# V1.net
KiCad netlist of a schematic drawn in EAGLE
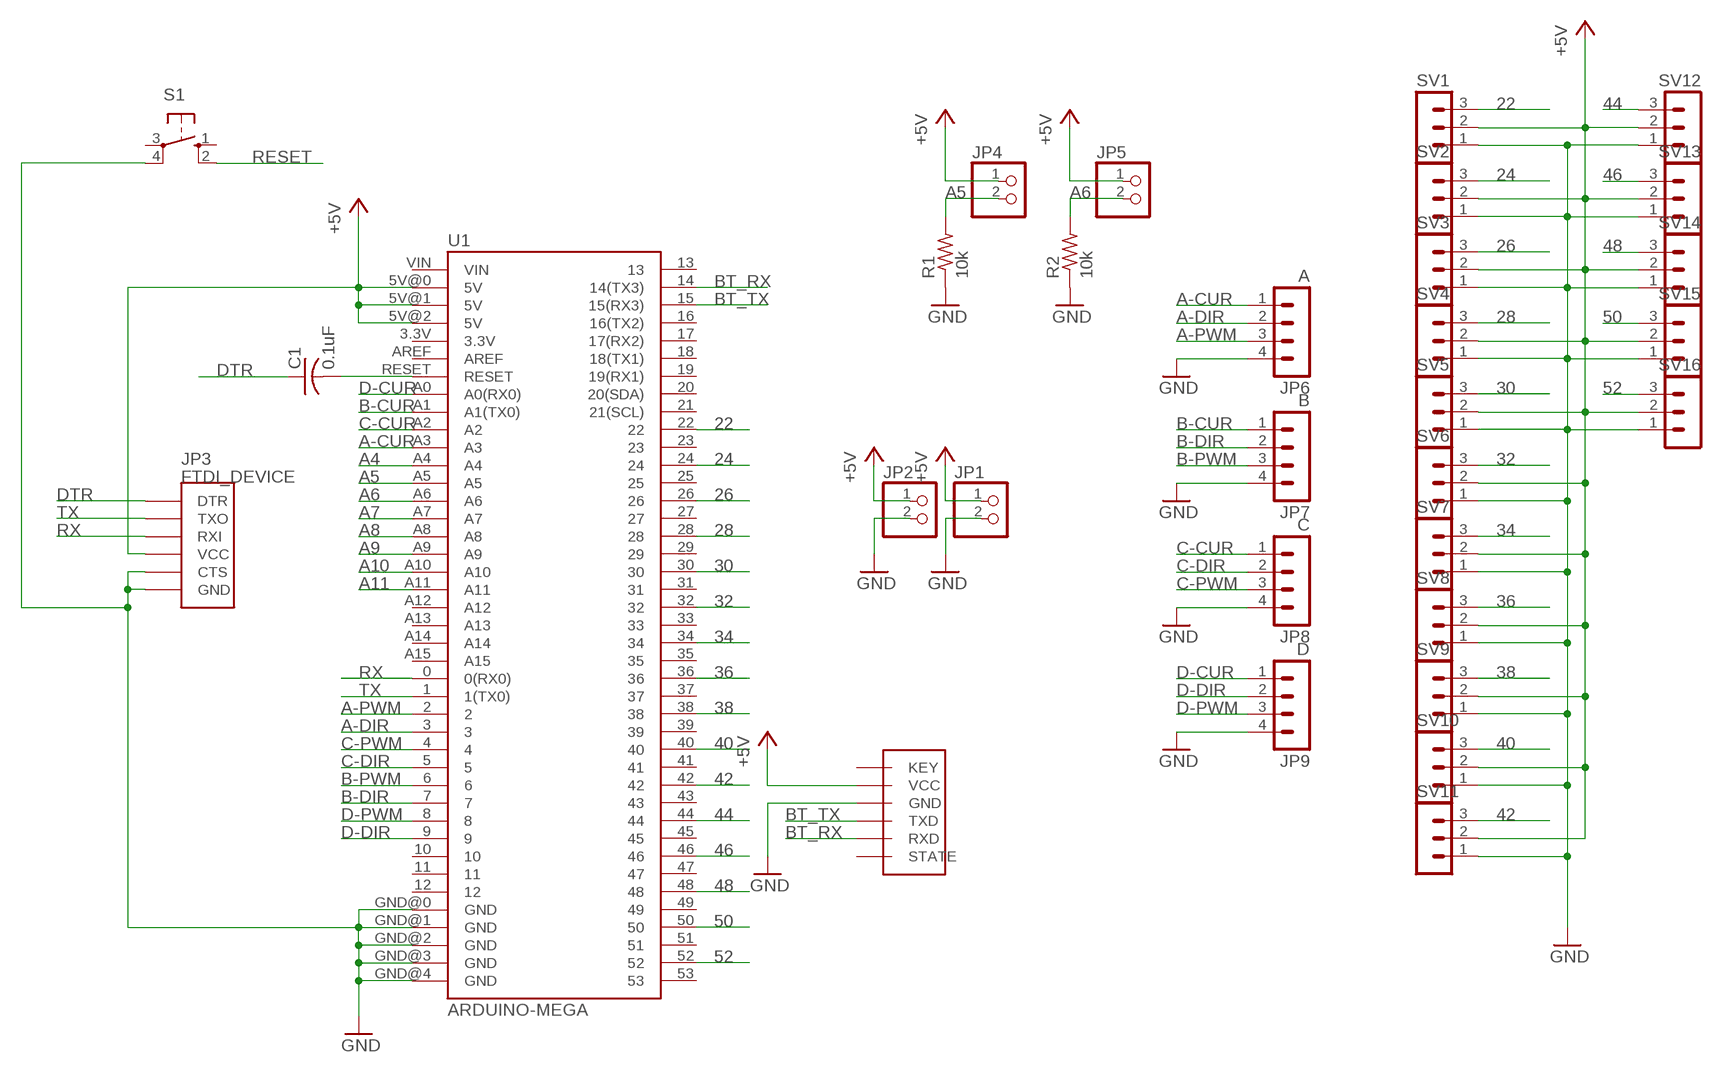
[diagram p0: schematic, sheet 1]

(export (version "E")
  (design (tool "Eeschema 10.0.6"))
  (components
    (comp (ref "BT1")
      (value "BT_MODULEVERTICAL")
      (footprint "eagle-import:BT_MODULE_V")
      (libsource (lib "eagle-import") (part "BT_MODULEVERTICAL"))
    )
    (comp (ref "C1")
      (value "0.1uF")
      (footprint "eagle-import:C025-024X044")
      (libsource (lib "eagle-import") (part "C-US025-024X044"))
    )
    (comp (ref "JP1")
      (value "PINHD-1X2")
      (footprint "eagle-import:1X02")
      (libsource (lib "eagle-import") (part "PINHD-1X2"))
    )
    (comp (ref "JP2")
      (value "PINHD-1X2")
      (footprint "eagle-import:1X02")
      (libsource (lib "eagle-import") (part "PINHD-1X2"))
    )
    (comp (ref "JP3")
      (value "FTDI_DEVICE")
      (footprint "eagle-import:FTDI_DEVICE_SIDE")
      (libsource (lib "eagle-import") (part "FTDI_DEVICE"))
    )
    (comp (ref "JP4")
      (value "PINHD-1X2")
      (footprint "eagle-import:1X02")
      (libsource (lib "eagle-import") (part "PINHD-1X2"))
    )
    (comp (ref "JP5")
      (value "PINHD-1X2")
      (footprint "eagle-import:1X02")
      (libsource (lib "eagle-import") (part "PINHD-1X2"))
    )
    (comp (ref "JP6")
      (value "A")
      (footprint "eagle-import:MA04-1")
      (libsource (lib "eagle-import") (part "MA04-1"))
    )
    (comp (ref "JP7")
      (value "B")
      (footprint "eagle-import:MA04-1")
      (libsource (lib "eagle-import") (part "MA04-1"))
    )
    (comp (ref "JP8")
      (value "C")
      (footprint "eagle-import:MA04-1")
      (libsource (lib "eagle-import") (part "MA04-1"))
    )
    (comp (ref "JP9")
      (value "D")
      (footprint "eagle-import:MA04-1")
      (libsource (lib "eagle-import") (part "MA04-1"))
    )
    (comp (ref "R1")
      (value "10k")
      (footprint "eagle-import:0204_7")
      (libsource (lib "eagle-import") (part "R-US_0204/7"))
    )
    (comp (ref "R2")
      (value "10k")
      (footprint "eagle-import:0204_7")
      (libsource (lib "eagle-import") (part "R-US_0204/7"))
    )
    (comp (ref "S1")
      (value "10-XX")
      (footprint "eagle-import:B3F-10XX")
      (fields (field (name "MPN") "B3F-1000"))
      (libsource (lib "eagle-import") (part "10-XX"))
    )
    (comp (ref "SV1")
      (value "MA03-1")
      (footprint "eagle-import:MA03-1")
      (libsource (lib "eagle-import") (part "MA03-1"))
    )
    (comp (ref "SV2")
      (value "MA03-1")
      (footprint "eagle-import:MA03-1")
      (libsource (lib "eagle-import") (part "MA03-1"))
    )
    (comp (ref "SV3")
      (value "MA03-1")
      (footprint "eagle-import:MA03-1")
      (libsource (lib "eagle-import") (part "MA03-1"))
    )
    (comp (ref "SV4")
      (value "MA03-1")
      (footprint "eagle-import:MA03-1")
      (libsource (lib "eagle-import") (part "MA03-1"))
    )
    (comp (ref "SV5")
      (value "MA03-1")
      (footprint "eagle-import:MA03-1")
      (libsource (lib "eagle-import") (part "MA03-1"))
    )
    (comp (ref "SV6")
      (value "MA03-1")
      (footprint "eagle-import:MA03-1")
      (libsource (lib "eagle-import") (part "MA03-1"))
    )
    (comp (ref "SV7")
      (value "MA03-1")
      (footprint "eagle-import:MA03-1")
      (libsource (lib "eagle-import") (part "MA03-1"))
    )
    (comp (ref "SV8")
      (value "MA03-1")
      (footprint "eagle-import:MA03-1")
      (libsource (lib "eagle-import") (part "MA03-1"))
    )
    (comp (ref "SV9")
      (value "MA03-1")
      (footprint "eagle-import:MA03-1")
      (libsource (lib "eagle-import") (part "MA03-1"))
    )
    (comp (ref "SV10")
      (value "MA03-1")
      (footprint "eagle-import:MA03-1")
      (libsource (lib "eagle-import") (part "MA03-1"))
    )
    (comp (ref "SV11")
      (value "MA03-1")
      (footprint "eagle-import:MA03-1")
      (libsource (lib "eagle-import") (part "MA03-1"))
    )
    (comp (ref "SV12")
      (value "MA03-1")
      (footprint "eagle-import:MA03-1")
      (libsource (lib "eagle-import") (part "MA03-1"))
    )
    (comp (ref "SV13")
      (value "MA03-1")
      (footprint "eagle-import:MA03-1")
      (libsource (lib "eagle-import") (part "MA03-1"))
    )
    (comp (ref "SV14")
      (value "MA03-1")
      (footprint "eagle-import:MA03-1")
      (libsource (lib "eagle-import") (part "MA03-1"))
    )
    (comp (ref "SV15")
      (value "MA03-1")
      (footprint "eagle-import:MA03-1")
      (libsource (lib "eagle-import") (part "MA03-1"))
    )
    (comp (ref "SV16")
      (value "MA03-1")
      (footprint "eagle-import:MA03-1")
      (libsource (lib "eagle-import") (part "MA03-1"))
    )
    (comp (ref "U1")
      (value "ARDUINO-MEGA")
      (footprint "eagle-import:ARDUINO_MEGA_PINS_ONLY")
      (libsource (lib "eagle-import") (part "ARDUINO-MEGA"))
    )
  )
  (nets
    (net (code "1") (name "+5V") (class "Default")
      (node (ref "BT1") (pin "VCC") (pinfunction "VCC_VCC") (pintype "bidirectional"))
      (node (ref "JP1") (pin "1") (pinfunction "1_1") (pintype "passive"))
      (node (ref "JP2") (pin "1") (pinfunction "1_1") (pintype "passive"))
      (node (ref "JP3") (pin "P$4") (pinfunction "VCC_P$4") (pintype "bidirectional"))
      (node (ref "JP4") (pin "1") (pinfunction "1_1") (pintype "passive"))
      (node (ref "JP5") (pin "1") (pinfunction "1_1") (pintype "passive"))
      (node (ref "SV1") (pin "2") (pinfunction "2_2") (pintype "passive"))
      (node (ref "SV10") (pin "2") (pinfunction "2_2") (pintype "passive"))
      (node (ref "SV11") (pin "2") (pinfunction "2_2") (pintype "passive"))
      (node (ref "SV12") (pin "2") (pinfunction "2_2") (pintype "passive"))
      (node (ref "SV13") (pin "2") (pinfunction "2_2") (pintype "passive"))
      (node (ref "SV14") (pin "2") (pinfunction "2_2") (pintype "passive"))
      (node (ref "SV15") (pin "2") (pinfunction "2_2") (pintype "passive"))
      (node (ref "SV16") (pin "2") (pinfunction "2_2") (pintype "passive"))
      (node (ref "SV2") (pin "2") (pinfunction "2_2") (pintype "passive"))
      (node (ref "SV3") (pin "2") (pinfunction "2_2") (pintype "passive"))
      (node (ref "SV4") (pin "2") (pinfunction "2_2") (pintype "passive"))
      (node (ref "SV5") (pin "2") (pinfunction "2_2") (pintype "passive"))
      (node (ref "SV6") (pin "2") (pinfunction "2_2") (pintype "passive"))
      (node (ref "SV7") (pin "2") (pinfunction "2_2") (pintype "passive"))
      (node (ref "SV8") (pin "2") (pinfunction "2_2") (pintype "passive"))
      (node (ref "SV9") (pin "2") (pinfunction "2_2") (pintype "passive"))
      (node (ref "U1") (pin "5V@0") (pinfunction "5V_5V@0") (pintype "bidirectional"))
      (node (ref "U1") (pin "5V@1") (pinfunction "5V_5V@1") (pintype "bidirectional"))
      (node (ref "U1") (pin "5V@2") (pinfunction "5V_5V@2") (pintype "bidirectional"))
    )
    (net (code "2") (name "/22") (class "Default")
      (node (ref "SV1") (pin "3") (pinfunction "3_3") (pintype "passive"))
      (node (ref "U1") (pin "22") (pinfunction "22_22") (pintype "bidirectional"))
    )
    (net (code "3") (name "/24") (class "Default")
      (node (ref "SV2") (pin "3") (pinfunction "3_3") (pintype "passive"))
      (node (ref "U1") (pin "24") (pinfunction "24_24") (pintype "bidirectional"))
    )
    (net (code "4") (name "/26") (class "Default")
      (node (ref "SV3") (pin "3") (pinfunction "3_3") (pintype "passive"))
      (node (ref "U1") (pin "26") (pinfunction "26_26") (pintype "bidirectional"))
    )
    (net (code "5") (name "/28") (class "Default")
      (node (ref "SV4") (pin "3") (pinfunction "3_3") (pintype "passive"))
      (node (ref "U1") (pin "28") (pinfunction "28_28") (pintype "bidirectional"))
    )
    (net (code "6") (name "/30") (class "Default")
      (node (ref "SV5") (pin "3") (pinfunction "3_3") (pintype "passive"))
      (node (ref "U1") (pin "30") (pinfunction "30_30") (pintype "bidirectional"))
    )
    (net (code "7") (name "/32") (class "Default")
      (node (ref "SV6") (pin "3") (pinfunction "3_3") (pintype "passive"))
      (node (ref "U1") (pin "32") (pinfunction "32_32") (pintype "bidirectional"))
    )
    (net (code "8") (name "/34") (class "Default")
      (node (ref "SV7") (pin "3") (pinfunction "3_3") (pintype "passive"))
      (node (ref "U1") (pin "34") (pinfunction "34_34") (pintype "bidirectional"))
    )
    (net (code "9") (name "/36") (class "Default")
      (node (ref "SV8") (pin "3") (pinfunction "3_3") (pintype "passive"))
      (node (ref "U1") (pin "36") (pinfunction "36_36") (pintype "bidirectional"))
    )
    (net (code "10") (name "/38") (class "Default")
      (node (ref "SV9") (pin "3") (pinfunction "3_3") (pintype "passive"))
      (node (ref "U1") (pin "38") (pinfunction "38_38") (pintype "bidirectional"))
    )
    (net (code "11") (name "/40") (class "Default")
      (node (ref "SV10") (pin "3") (pinfunction "3_3") (pintype "passive"))
      (node (ref "U1") (pin "40") (pinfunction "40_40") (pintype "bidirectional"))
    )
    (net (code "12") (name "/42") (class "Default")
      (node (ref "SV11") (pin "3") (pinfunction "3_3") (pintype "passive"))
      (node (ref "U1") (pin "42") (pinfunction "42_42") (pintype "bidirectional"))
    )
    (net (code "13") (name "/44") (class "Default")
      (node (ref "SV12") (pin "3") (pinfunction "3_3") (pintype "passive"))
      (node (ref "U1") (pin "44") (pinfunction "44_44") (pintype "bidirectional"))
    )
    (net (code "14") (name "/46") (class "Default")
      (node (ref "SV13") (pin "3") (pinfunction "3_3") (pintype "passive"))
      (node (ref "U1") (pin "46") (pinfunction "46_46") (pintype "bidirectional"))
    )
    (net (code "15") (name "/48") (class "Default")
      (node (ref "SV14") (pin "3") (pinfunction "3_3") (pintype "passive"))
      (node (ref "U1") (pin "48") (pinfunction "48_48") (pintype "bidirectional"))
    )
    (net (code "16") (name "/50") (class "Default")
      (node (ref "SV15") (pin "3") (pinfunction "3_3") (pintype "passive"))
      (node (ref "U1") (pin "50") (pinfunction "50_50") (pintype "bidirectional"))
    )
    (net (code "17") (name "/52") (class "Default")
      (node (ref "SV16") (pin "3") (pinfunction "3_3") (pintype "passive"))
      (node (ref "U1") (pin "52") (pinfunction "52_52") (pintype "bidirectional"))
    )
    (net (code "18") (name "/A-CUR") (class "Default")
      (node (ref "JP6") (pin "1") (pinfunction "1_1") (pintype "passive"))
      (node (ref "U1") (pin "A3") (pinfunction "A3_A3") (pintype "bidirectional"))
    )
    (net (code "19") (name "/A-DIR") (class "Default")
      (node (ref "JP6") (pin "2") (pinfunction "2_2") (pintype "passive"))
      (node (ref "U1") (pin "3") (pinfunction "3_3") (pintype "bidirectional"))
    )
    (net (code "20") (name "/A-PWM") (class "Default")
      (node (ref "JP6") (pin "3") (pinfunction "3_3") (pintype "passive"))
      (node (ref "U1") (pin "2") (pinfunction "2_2") (pintype "bidirectional"))
    )
    (net (code "21") (name "/A4") (class "Default")
      (node (ref "U1") (pin "A4") (pinfunction "A4_A4") (pintype "bidirectional"))
    )
    (net (code "22") (name "/A5") (class "Default")
      (node (ref "JP4") (pin "2") (pinfunction "2_2") (pintype "passive"))
      (node (ref "R1") (pin "2") (pinfunction "2_2") (pintype "passive"))
      (node (ref "U1") (pin "A5") (pinfunction "A5_A5") (pintype "bidirectional"))
    )
    (net (code "23") (name "/A6") (class "Default")
      (node (ref "JP5") (pin "2") (pinfunction "2_2") (pintype "passive"))
      (node (ref "R2") (pin "2") (pinfunction "2_2") (pintype "passive"))
      (node (ref "U1") (pin "A6") (pinfunction "A6_A6") (pintype "bidirectional"))
    )
    (net (code "24") (name "/A7") (class "Default")
      (node (ref "U1") (pin "A7") (pinfunction "A7_A7") (pintype "bidirectional"))
    )
    (net (code "25") (name "/A8") (class "Default")
      (node (ref "U1") (pin "A8") (pinfunction "A8_A8") (pintype "bidirectional"))
    )
    (net (code "26") (name "/A9") (class "Default")
      (node (ref "U1") (pin "A9") (pinfunction "A9_A9") (pintype "bidirectional"))
    )
    (net (code "27") (name "/A10") (class "Default")
      (node (ref "U1") (pin "A10") (pinfunction "A10_A10") (pintype "bidirectional"))
    )
    (net (code "28") (name "/A11") (class "Default")
      (node (ref "U1") (pin "A11") (pinfunction "A11_A11") (pintype "bidirectional"))
    )
    (net (code "29") (name "/B-CUR") (class "Default")
      (node (ref "JP7") (pin "1") (pinfunction "1_1") (pintype "passive"))
      (node (ref "U1") (pin "A1") (pinfunction "A1(TX0)_A1") (pintype "bidirectional"))
    )
    (net (code "30") (name "/B-DIR") (class "Default")
      (node (ref "JP7") (pin "2") (pinfunction "2_2") (pintype "passive"))
      (node (ref "U1") (pin "7") (pinfunction "7_7") (pintype "bidirectional"))
    )
    (net (code "31") (name "/B-PWM") (class "Default")
      (node (ref "JP7") (pin "3") (pinfunction "3_3") (pintype "passive"))
      (node (ref "U1") (pin "6") (pinfunction "6_6") (pintype "bidirectional"))
    )
    (net (code "32") (name "/BT_RX") (class "Default")
      (node (ref "BT1") (pin "RXD") (pinfunction "RXD_RXD") (pintype "bidirectional"))
      (node (ref "U1") (pin "14") (pinfunction "14(TX3)_14") (pintype "bidirectional"))
    )
    (net (code "33") (name "/BT_TX") (class "Default")
      (node (ref "BT1") (pin "TXD") (pinfunction "TXD_TXD") (pintype "bidirectional"))
      (node (ref "U1") (pin "15") (pinfunction "15(RX3)_15") (pintype "bidirectional"))
    )
    (net (code "34") (name "/C-CUR") (class "Default")
      (node (ref "JP8") (pin "1") (pinfunction "1_1") (pintype "passive"))
      (node (ref "U1") (pin "A2") (pinfunction "A2_A2") (pintype "bidirectional"))
    )
    (net (code "35") (name "/C-DIR") (class "Default")
      (node (ref "JP8") (pin "2") (pinfunction "2_2") (pintype "passive"))
      (node (ref "U1") (pin "5") (pinfunction "5_5") (pintype "bidirectional"))
    )
    (net (code "36") (name "/C-PWM") (class "Default")
      (node (ref "JP8") (pin "3") (pinfunction "3_3") (pintype "passive"))
      (node (ref "U1") (pin "4") (pinfunction "4_4") (pintype "bidirectional"))
    )
    (net (code "37") (name "/D-CUR") (class "Default")
      (node (ref "JP9") (pin "1") (pinfunction "1_1") (pintype "passive"))
      (node (ref "U1") (pin "A0") (pinfunction "A0(RX0)_A0") (pintype "bidirectional"))
    )
    (net (code "38") (name "/D-DIR") (class "Default")
      (node (ref "JP9") (pin "2") (pinfunction "2_2") (pintype "passive"))
      (node (ref "U1") (pin "9") (pinfunction "9_9") (pintype "bidirectional"))
    )
    (net (code "39") (name "/D-PWM") (class "Default")
      (node (ref "JP9") (pin "3") (pinfunction "3_3") (pintype "passive"))
      (node (ref "U1") (pin "8") (pinfunction "8_8") (pintype "bidirectional"))
    )
    (net (code "40") (name "/DTR") (class "Default")
      (node (ref "C1") (pin "1") (pinfunction "1_1") (pintype "passive"))
      (node (ref "JP3") (pin "P$1") (pinfunction "DTR_P$1") (pintype "bidirectional"))
    )
    (net (code "41") (name "/RESET") (class "Default")
      (node (ref "C1") (pin "2") (pinfunction "2_2") (pintype "passive"))
      (node (ref "S1") (pin "2") (pinfunction "S1_2") (pintype "passive"))
      (node (ref "U1") (pin "RESET") (pinfunction "RESET_RESET") (pintype "bidirectional"))
    )
    (net (code "42") (name "/RX") (class "Default")
      (node (ref "JP3") (pin "P$3") (pinfunction "RXI_P$3") (pintype "bidirectional"))
      (node (ref "U1") (pin "0") (pinfunction "0(RX0)_0") (pintype "bidirectional"))
    )
    (net (code "43") (name "/TX") (class "Default")
      (node (ref "JP3") (pin "P$2") (pinfunction "TXO_P$2") (pintype "bidirectional"))
      (node (ref "U1") (pin "1") (pinfunction "1(TX0)_1") (pintype "bidirectional"))
    )
    (net (code "44") (name "GND") (class "Default")
      (node (ref "BT1") (pin "GND") (pinfunction "GND_GND") (pintype "bidirectional"))
      (node (ref "JP1") (pin "2") (pinfunction "2_2") (pintype "passive"))
      (node (ref "JP2") (pin "2") (pinfunction "2_2") (pintype "passive"))
      (node (ref "JP3") (pin "P$5") (pinfunction "CTS_P$5") (pintype "bidirectional"))
      (node (ref "JP3") (pin "P$6") (pinfunction "GND_P$6") (pintype "bidirectional"))
      (node (ref "JP6") (pin "4") (pinfunction "4_4") (pintype "passive"))
      (node (ref "JP7") (pin "4") (pinfunction "4_4") (pintype "passive"))
      (node (ref "JP8") (pin "4") (pinfunction "4_4") (pintype "passive"))
      (node (ref "JP9") (pin "4") (pinfunction "4_4") (pintype "passive"))
      (node (ref "R1") (pin "1") (pinfunction "1_1") (pintype "passive"))
      (node (ref "R2") (pin "1") (pinfunction "1_1") (pintype "passive"))
      (node (ref "S1") (pin "4") (pinfunction "P1_4") (pintype "passive"))
      (node (ref "SV1") (pin "1") (pinfunction "1_1") (pintype "passive"))
      (node (ref "SV10") (pin "1") (pinfunction "1_1") (pintype "passive"))
      (node (ref "SV11") (pin "1") (pinfunction "1_1") (pintype "passive"))
      (node (ref "SV12") (pin "1") (pinfunction "1_1") (pintype "passive"))
      (node (ref "SV13") (pin "1") (pinfunction "1_1") (pintype "passive"))
      (node (ref "SV14") (pin "1") (pinfunction "1_1") (pintype "passive"))
      (node (ref "SV15") (pin "1") (pinfunction "1_1") (pintype "passive"))
      (node (ref "SV16") (pin "1") (pinfunction "1_1") (pintype "passive"))
      (node (ref "SV2") (pin "1") (pinfunction "1_1") (pintype "passive"))
      (node (ref "SV3") (pin "1") (pinfunction "1_1") (pintype "passive"))
      (node (ref "SV4") (pin "1") (pinfunction "1_1") (pintype "passive"))
      (node (ref "SV5") (pin "1") (pinfunction "1_1") (pintype "passive"))
      (node (ref "SV6") (pin "1") (pinfunction "1_1") (pintype "passive"))
      (node (ref "SV7") (pin "1") (pinfunction "1_1") (pintype "passive"))
      (node (ref "SV8") (pin "1") (pinfunction "1_1") (pintype "passive"))
      (node (ref "SV9") (pin "1") (pinfunction "1_1") (pintype "passive"))
      (node (ref "U1") (pin "GND@0") (pinfunction "GND_GND@0") (pintype "bidirectional"))
      (node (ref "U1") (pin "GND@1") (pinfunction "GND_GND@1") (pintype "bidirectional"))
      (node (ref "U1") (pin "GND@2") (pinfunction "GND_GND@2") (pintype "bidirectional"))
      (node (ref "U1") (pin "GND@3") (pinfunction "GND_GND@3") (pintype "bidirectional"))
      (node (ref "U1") (pin "GND@4") (pinfunction "GND_GND@4") (pintype "bidirectional"))
    )
    (net (code "45") (name "unconnected-(BT1-PadKEY)") (class "Default")
      (node (ref "BT1") (pin "KEY") (pinfunction "KEY_KEY") (pintype "bidirectional"))
    )
    (net (code "46") (name "unconnected-(BT1-PadSTATE)") (class "Default")
      (node (ref "BT1") (pin "STATE") (pinfunction "STATE_STATE") (pintype "bidirectional"))
    )
    (net (code "47") (name "unconnected-(S1-P-Pad3)") (class "Default")
      (node (ref "S1") (pin "3") (pinfunction "P_3") (pintype "passive"))
    )
    (net (code "48") (name "unconnected-(S1-S-Pad1)") (class "Default")
      (node (ref "S1") (pin "1") (pinfunction "S_1") (pintype "passive"))
    )
    (net (code "49") (name "unconnected-(U1-16(TX2)-Pad16)") (class "Default")
      (node (ref "U1") (pin "16") (pinfunction "16(TX2)_16") (pintype "bidirectional"))
    )
    (net (code "50") (name "unconnected-(U1-17(RX2)-Pad17)") (class "Default")
      (node (ref "U1") (pin "17") (pinfunction "17(RX2)_17") (pintype "bidirectional"))
    )
    (net (code "51") (name "unconnected-(U1-18(TX1)-Pad18)") (class "Default")
      (node (ref "U1") (pin "18") (pinfunction "18(TX1)_18") (pintype "bidirectional"))
    )
    (net (code "52") (name "unconnected-(U1-19(RX1)-Pad19)") (class "Default")
      (node (ref "U1") (pin "19") (pinfunction "19(RX1)_19") (pintype "bidirectional"))
    )
    (net (code "53") (name "unconnected-(U1-20(SDA)-Pad20)") (class "Default")
      (node (ref "U1") (pin "20") (pinfunction "20(SDA)_20") (pintype "bidirectional"))
    )
    (net (code "54") (name "unconnected-(U1-21(SCL)-Pad21)") (class "Default")
      (node (ref "U1") (pin "21") (pinfunction "21(SCL)_21") (pintype "bidirectional"))
    )
    (net (code "55") (name "unconnected-(U1-Pad3.3V)") (class "Default")
      (node (ref "U1") (pin "3.3V") (pinfunction "3.3V_3.3V") (pintype "bidirectional"))
    )
    (net (code "56") (name "unconnected-(U1-Pad10)") (class "Default")
      (node (ref "U1") (pin "10") (pinfunction "10_10") (pintype "bidirectional"))
    )
    (net (code "57") (name "unconnected-(U1-Pad11)") (class "Default")
      (node (ref "U1") (pin "11") (pinfunction "11_11") (pintype "bidirectional"))
    )
    (net (code "58") (name "unconnected-(U1-Pad12)") (class "Default")
      (node (ref "U1") (pin "12") (pinfunction "12_12") (pintype "bidirectional"))
    )
    (net (code "59") (name "unconnected-(U1-Pad13)") (class "Default")
      (node (ref "U1") (pin "13") (pinfunction "13_13") (pintype "bidirectional"))
    )
    (net (code "60") (name "unconnected-(U1-Pad23)") (class "Default")
      (node (ref "U1") (pin "23") (pinfunction "23_23") (pintype "bidirectional"))
    )
    (net (code "61") (name "unconnected-(U1-Pad25)") (class "Default")
      (node (ref "U1") (pin "25") (pinfunction "25_25") (pintype "bidirectional"))
    )
    (net (code "62") (name "unconnected-(U1-Pad27)") (class "Default")
      (node (ref "U1") (pin "27") (pinfunction "27_27") (pintype "bidirectional"))
    )
    (net (code "63") (name "unconnected-(U1-Pad29)") (class "Default")
      (node (ref "U1") (pin "29") (pinfunction "29_29") (pintype "bidirectional"))
    )
    (net (code "64") (name "unconnected-(U1-Pad31)") (class "Default")
      (node (ref "U1") (pin "31") (pinfunction "31_31") (pintype "bidirectional"))
    )
    (net (code "65") (name "unconnected-(U1-Pad33)") (class "Default")
      (node (ref "U1") (pin "33") (pinfunction "33_33") (pintype "bidirectional"))
    )
    (net (code "66") (name "unconnected-(U1-Pad35)") (class "Default")
      (node (ref "U1") (pin "35") (pinfunction "35_35") (pintype "bidirectional"))
    )
    (net (code "67") (name "unconnected-(U1-Pad37)") (class "Default")
      (node (ref "U1") (pin "37") (pinfunction "37_37") (pintype "bidirectional"))
    )
    (net (code "68") (name "unconnected-(U1-Pad39)") (class "Default")
      (node (ref "U1") (pin "39") (pinfunction "39_39") (pintype "bidirectional"))
    )
    (net (code "69") (name "unconnected-(U1-Pad41)") (class "Default")
      (node (ref "U1") (pin "41") (pinfunction "41_41") (pintype "bidirectional"))
    )
    (net (code "70") (name "unconnected-(U1-Pad43)") (class "Default")
      (node (ref "U1") (pin "43") (pinfunction "43_43") (pintype "bidirectional"))
    )
    (net (code "71") (name "unconnected-(U1-Pad45)") (class "Default")
      (node (ref "U1") (pin "45") (pinfunction "45_45") (pintype "bidirectional"))
    )
    (net (code "72") (name "unconnected-(U1-Pad47)") (class "Default")
      (node (ref "U1") (pin "47") (pinfunction "47_47") (pintype "bidirectional"))
    )
    (net (code "73") (name "unconnected-(U1-Pad49)") (class "Default")
      (node (ref "U1") (pin "49") (pinfunction "49_49") (pintype "bidirectional"))
    )
    (net (code "74") (name "unconnected-(U1-Pad51)") (class "Default")
      (node (ref "U1") (pin "51") (pinfunction "51_51") (pintype "bidirectional"))
    )
    (net (code "75") (name "unconnected-(U1-Pad53)") (class "Default")
      (node (ref "U1") (pin "53") (pinfunction "53_53") (pintype "bidirectional"))
    )
    (net (code "76") (name "unconnected-(U1-PadA12)") (class "Default")
      (node (ref "U1") (pin "A12") (pinfunction "A12_A12") (pintype "bidirectional"))
    )
    (net (code "77") (name "unconnected-(U1-PadA13)") (class "Default")
      (node (ref "U1") (pin "A13") (pinfunction "A13_A13") (pintype "bidirectional"))
    )
    (net (code "78") (name "unconnected-(U1-PadA14)") (class "Default")
      (node (ref "U1") (pin "A14") (pinfunction "A14_A14") (pintype "bidirectional"))
    )
    (net (code "79") (name "unconnected-(U1-PadA15)") (class "Default")
      (node (ref "U1") (pin "A15") (pinfunction "A15_A15") (pintype "bidirectional"))
    )
    (net (code "80") (name "unconnected-(U1-PadAREF)") (class "Default")
      (node (ref "U1") (pin "AREF") (pinfunction "AREF_AREF") (pintype "bidirectional"))
    )
    (net (code "81") (name "unconnected-(U1-PadVIN)") (class "Default")
      (node (ref "U1") (pin "VIN") (pinfunction "VIN_VIN") (pintype "bidirectional"))
    )
  )
)
